# ProPrj_24_U202442553_2025-12-01.net
KiCad netlist of a schematic drawn in EasyEDA Pro
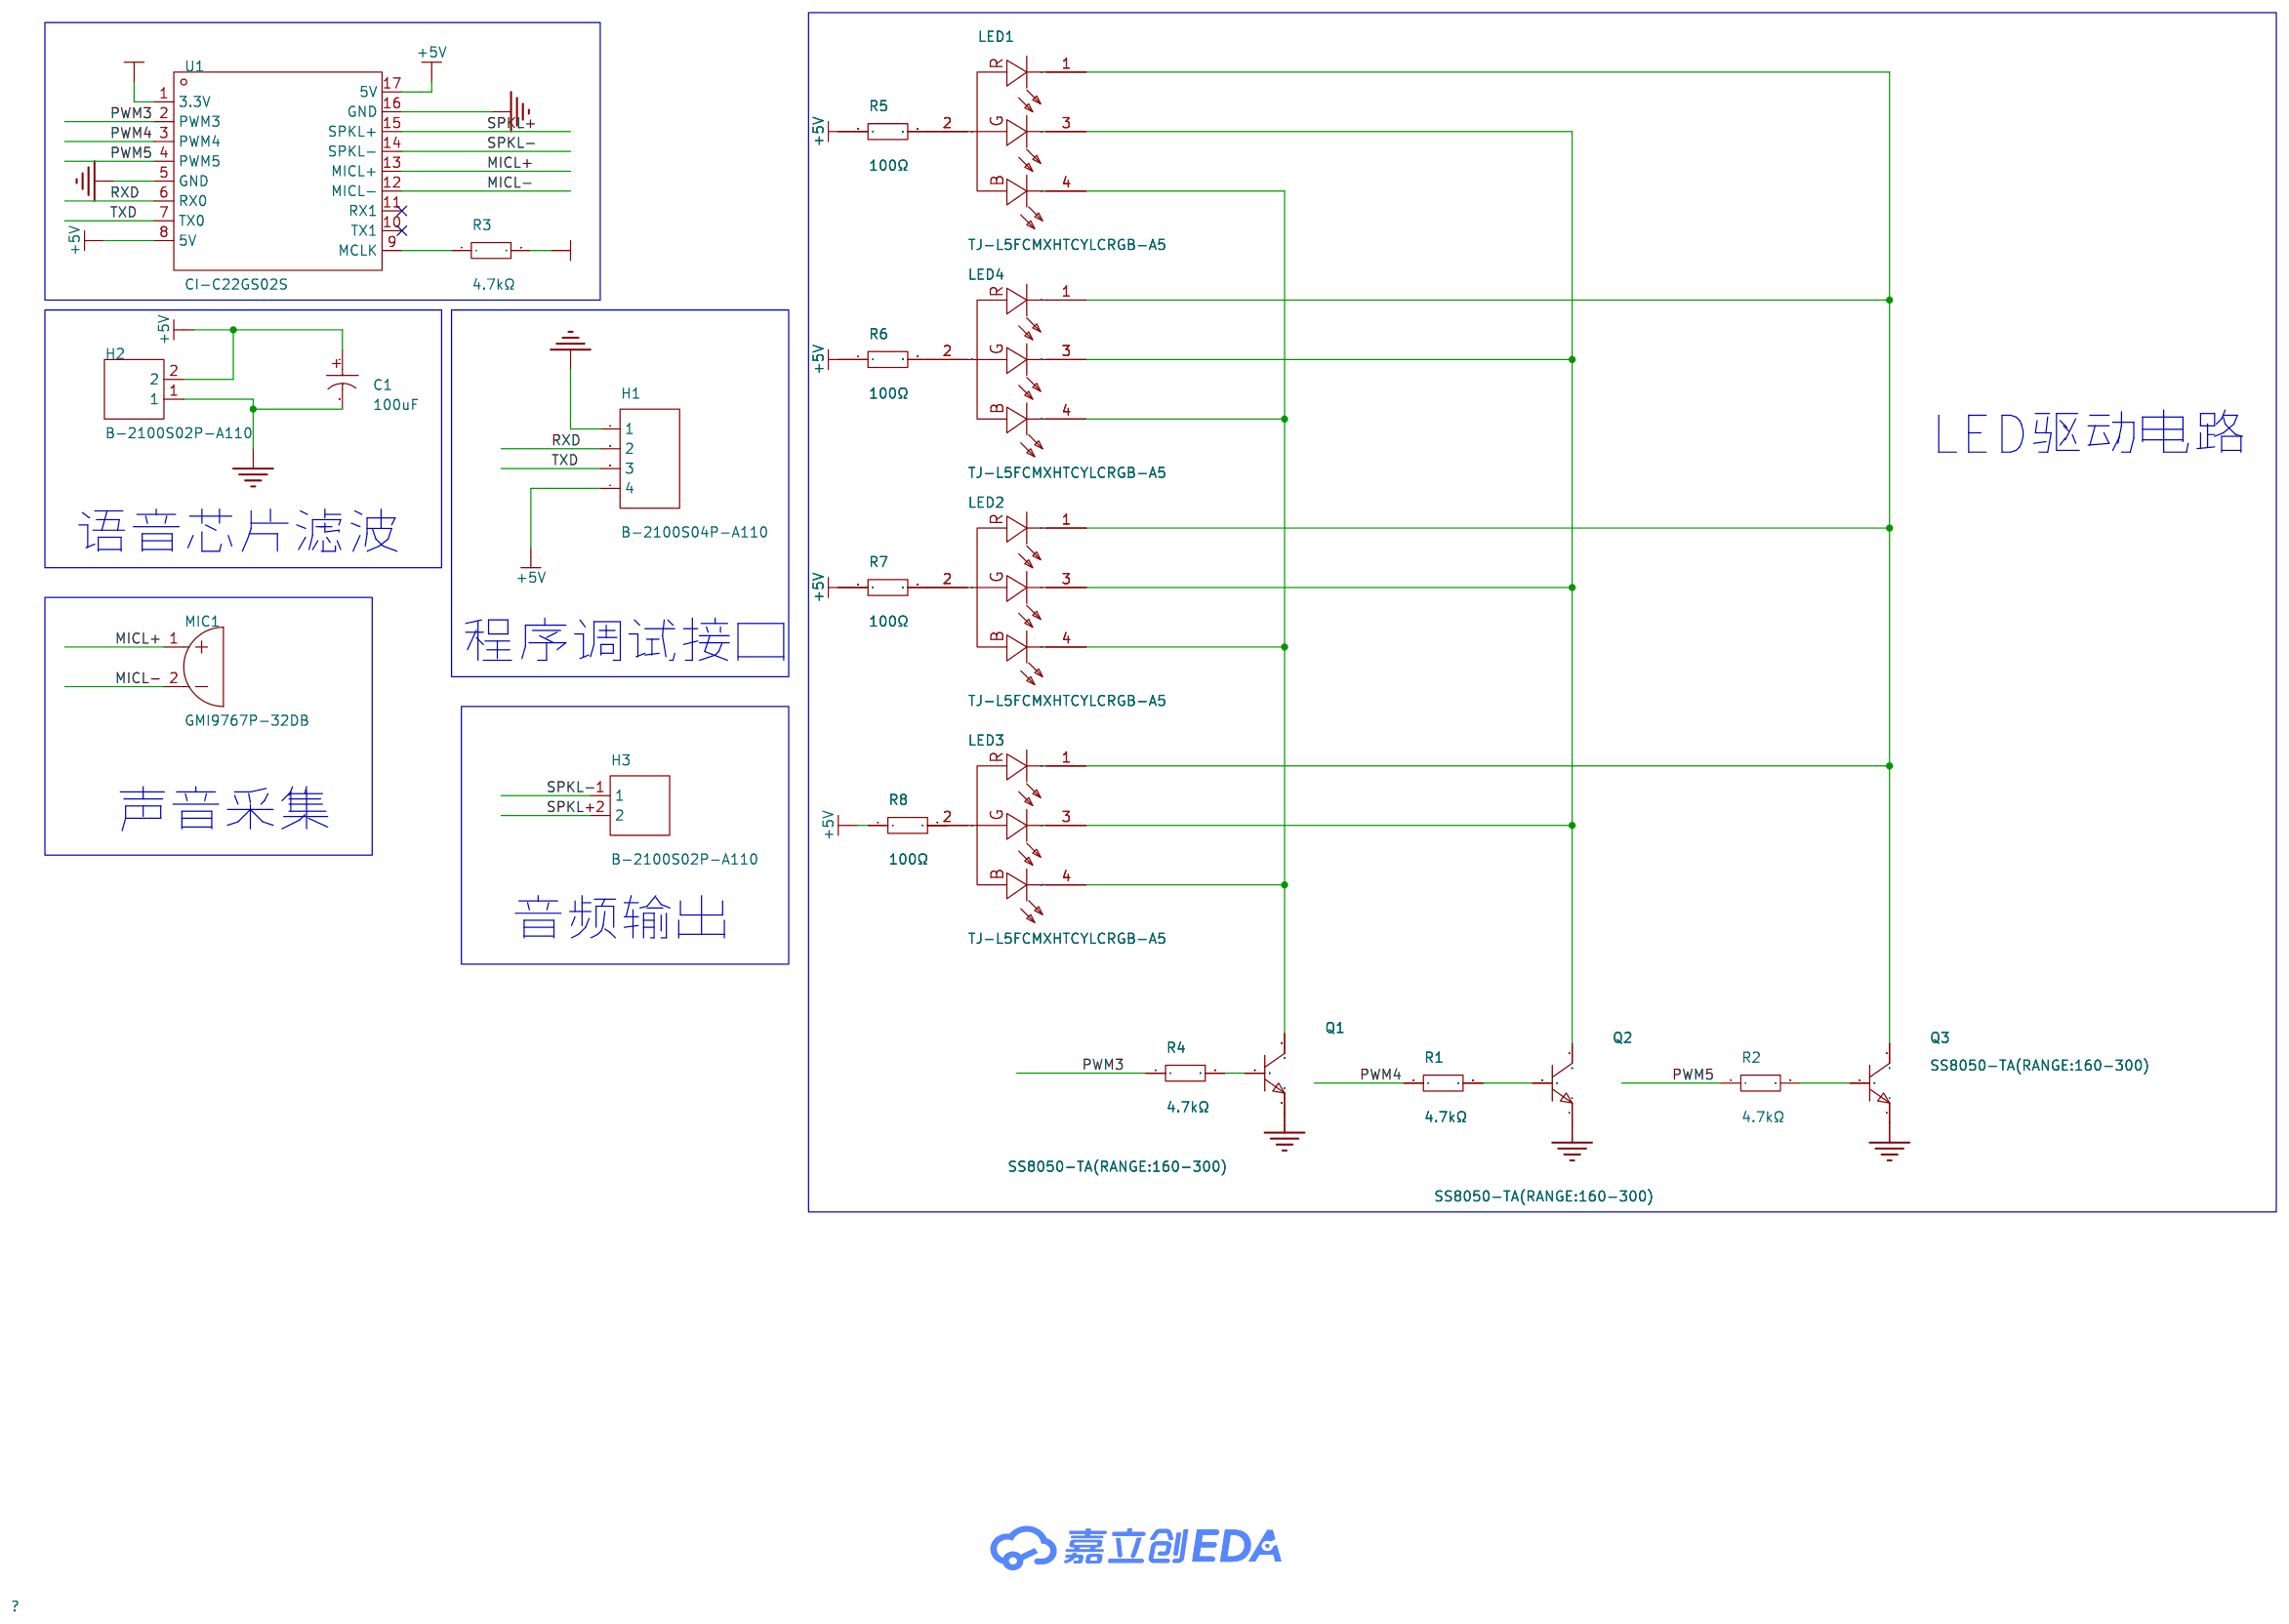
[diagram p0: schematic sheet]

(export (version "E")
  (design (tool "Eeschema 10.0.6"))
  (components
    (comp (ref "C1")
      (value "100uF")
      (footprint "easyedapro:CAP-TH_BD5.0-P2.00-D0.8-FD")
      (description "容值:100uF;精度:±20%;额定电压:16V;纹波电流:125mA@120Hz;等效串联电阻(ESR):-;")
      (fields
        (field (name "Manufacturer Part") "KM107M016D11RR0VH2FP0")
        (field (name "Manufacturer") "Chengx(承兴)")
      )
      (libsource (lib "easyedapro") (part "100uF 16V 5*11"))
    )
    (comp (ref "H1")
      (value "B-2100S04P-A110")
      (footprint "easyedapro:HDR-TH_4P-P2.54-V-M")
      (fields (field (name "Manufacturer") "Ckmtw(灿科盟)"))
      (libsource (lib "easyedapro") (part "Header-Male-2.54_1x4"))
    )
    (comp (ref "H2")
      (value "B-2100S02P-A110")
      (footprint "easyedapro:HDR-TH_2P-P2.54-V-M-1")
      (fields (field (name "Manufacturer") "Ckmtw(灿科盟)"))
      (libsource (lib "easyedapro") (part "210S-1*2P L=11.6MMGold-plated black"))
    )
    (comp (ref "H3")
      (value "B-2100S02P-A110")
      (footprint "easyedapro:HDR-TH_2P-P2.54-V-M-1")
      (fields (field (name "Manufacturer") "Ckmtw(灿科盟)"))
      (libsource (lib "easyedapro") (part "210S-1*2P L=11.6MMGold-plated black"))
    )
    (comp (ref "LED1")
      (value "TJ-L5FCMXHTCYLCRGB-A5")
      (footprint "easyedapro:LED-TH_4P-BD5.8-P1.30")
      (description "F5草帽RGB,直插RGB,F5草帽三色RGB")
      (fields (field (name "Manufacturer") "TOGIALED(统佳)"))
      (libsource (lib "easyedapro") (part "TJ-L5FCMXHTCYLCRGB-A5"))
    )
    (comp (ref "LED2")
      (value "TJ-L5FCMXHTCYLCRGB-A5")
      (footprint "easyedapro:LED-TH_4P-BD5.8-P1.30")
      (description "F5草帽RGB,直插RGB,F5草帽三色RGB")
      (fields (field (name "Manufacturer") "TOGIALED(统佳)"))
      (libsource (lib "easyedapro") (part "TJ-L5FCMXHTCYLCRGB-A5"))
    )
    (comp (ref "LED3")
      (value "TJ-L5FCMXHTCYLCRGB-A5")
      (footprint "easyedapro:LED-TH_4P-BD5.8-P1.30")
      (description "F5草帽RGB,直插RGB,F5草帽三色RGB")
      (fields (field (name "Manufacturer") "TOGIALED(统佳)"))
      (libsource (lib "easyedapro") (part "TJ-L5FCMXHTCYLCRGB-A5"))
    )
    (comp (ref "LED4")
      (value "TJ-L5FCMXHTCYLCRGB-A5")
      (footprint "easyedapro:LED-TH_4P-BD5.8-P1.30")
      (description "F5草帽RGB,直插RGB,F5草帽三色RGB")
      (fields (field (name "Manufacturer") "TOGIALED(统佳)"))
      (libsource (lib "easyedapro") (part "TJ-L5FCMXHTCYLCRGB-A5"))
    )
    (comp (ref "MIC1")
      (value "GMI9767P-32DB")
      (footprint "easyedapro:MIC-TH_BD9.7-P2.54-D0.8-L-FD")
      (description "指向性:全指向;输出阻抗:2.2kΩ;信噪比:58dB;灵敏度:-32dB;")
      (fields (field (name "Manufacturer") "INGHAi(赢海)"))
      (libsource (lib "easyedapro") (part "GMI9767P-32DB"))
    )
    (comp (ref "Q1")
      (value "SS8050-TA(RANGE:160-300)")
      (footprint "easyedapro:TO-92-3_L4.8-W3.7-P2.54-L")
      (description "晶体管类型:NPN;集电极电流(Ic):1.5A;集射极击穿电压(Vceo):25V;耗散功率(Pd):1W;直流电流增益(hFE):160@800mA,1V;")
      (fields (field (name "Manufacturer") "CJ(江苏长电/长晶)"))
      (libsource (lib "easyedapro") (part "SS8050_C80297"))
    )
    (comp (ref "Q2")
      (value "SS8050-TA(RANGE:160-300)")
      (footprint "easyedapro:TO-92-3_L4.8-W3.7-P2.54-L")
      (description "晶体管类型:NPN;集电极电流(Ic):1.5A;集射极击穿电压(Vceo):25V;耗散功率(Pd):1W;直流电流增益(hFE):160@800mA,1V;")
      (fields (field (name "Manufacturer") "CJ(江苏长电/长晶)"))
      (libsource (lib "easyedapro") (part "SS8050_C80297"))
    )
    (comp (ref "Q3")
      (value "SS8050-TA(RANGE:160-300)")
      (footprint "easyedapro:TO-92-3_L4.8-W3.7-P2.54-L")
      (description "晶体管类型:NPN;集电极电流(Ic):1.5A;集射极击穿电压(Vceo):25V;耗散功率(Pd):1W;直流电流增益(hFE):160@800mA,1V;")
      (fields (field (name "Manufacturer") "CJ(江苏长电/长晶)"))
      (libsource (lib "easyedapro") (part "SS8050_C80297"))
    )
    (comp (ref "R1")
      (value "4.7kΩ")
      (footprint "easyedapro:RES-TH_BD2.3-L6.5-P10.50-D0.5")
      (description "电阻类型:金属膜电阻;阻值:4.7kΩ;精度:±1%;功率:250mW;温度系数:±100ppm/°C;")
      (fields
        (field (name "Manufacturer Part") "MF1/4W-4.7KΩ±1% T")
        (field (name "Manufacturer") "CCO(千志电子)")
      )
      (libsource (lib "easyedapro") (part "MF1/4W-4.7KΩ±1% T52"))
    )
    (comp (ref "R2")
      (value "4.7kΩ")
      (footprint "easyedapro:RES-TH_BD2.3-L6.5-P10.50-D0.5")
      (description "电阻类型:金属膜电阻;阻值:4.7kΩ;精度:±1%;功率:250mW;温度系数:±100ppm/°C;")
      (fields
        (field (name "Manufacturer Part") "MF1/4W-4.7KΩ±1% T")
        (field (name "Manufacturer") "CCO(千志电子)")
      )
      (libsource (lib "easyedapro") (part "MF1/4W-4.7KΩ±1% T52"))
    )
    (comp (ref "R3")
      (value "4.7kΩ")
      (footprint "easyedapro:RES-TH_BD2.3-L6.5-P10.50-D0.5")
      (description "电阻类型:金属膜电阻;阻值:4.7kΩ;精度:±1%;功率:250mW;温度系数:±100ppm/°C;")
      (fields
        (field (name "Manufacturer Part") "MF1/4W-4.7KΩ±1% T")
        (field (name "Manufacturer") "CCO(千志电子)")
      )
      (libsource (lib "easyedapro") (part "MF1/4W-4.7KΩ±1% T52"))
    )
    (comp (ref "R4")
      (value "4.7kΩ")
      (footprint "easyedapro:RES-TH_BD2.3-L6.5-P10.50-D0.5")
      (description "电阻类型:金属膜电阻;阻值:4.7kΩ;精度:±1%;功率:250mW;温度系数:±100ppm/°C;")
      (fields
        (field (name "Manufacturer Part") "MF1/4W-4.7KΩ±1% T")
        (field (name "Manufacturer") "CCO(千志电子)")
      )
      (libsource (lib "easyedapro") (part "MF1/4W-4.7KΩ±1% T52"))
    )
    (comp (ref "R5")
      (value "100Ω")
      (footprint "easyedapro:RES-TH_BD3.3-L9.0-P13.00-D0.6")
      (description "电阻类型:金属膜电阻;阻值:100Ω;精度:±1%;功率:500mW;温度系数:±50ppm/°C;")
      (fields
        (field (name "Manufacturer Part") "RN1/2W100ΩFT/BA1")
        (field (name "Manufacturer") "Tyohm(幸亚电阻)")
      )
      (libsource (lib "easyedapro") (part "RN1/2W100ΩFT/BA1"))
    )
    (comp (ref "R6")
      (value "100Ω")
      (footprint "easyedapro:RES-TH_BD3.3-L9.0-P13.00-D0.6")
      (description "电阻类型:金属膜电阻;阻值:100Ω;精度:±1%;功率:500mW;温度系数:±50ppm/°C;")
      (fields
        (field (name "Manufacturer Part") "RN1/2W100ΩFT/BA1")
        (field (name "Manufacturer") "Tyohm(幸亚电阻)")
      )
      (libsource (lib "easyedapro") (part "RN1/2W100ΩFT/BA1"))
    )
    (comp (ref "R7")
      (value "100Ω")
      (footprint "easyedapro:RES-TH_BD3.3-L9.0-P13.00-D0.6")
      (description "电阻类型:金属膜电阻;阻值:100Ω;精度:±1%;功率:500mW;温度系数:±50ppm/°C;")
      (fields
        (field (name "Manufacturer Part") "RN1/2W100ΩFT/BA1")
        (field (name "Manufacturer") "Tyohm(幸亚电阻)")
      )
      (libsource (lib "easyedapro") (part "RN1/2W100ΩFT/BA1"))
    )
    (comp (ref "R8")
      (value "100Ω")
      (footprint "easyedapro:RES-TH_BD3.3-L9.0-P13.00-D0.6")
      (description "电阻类型:金属膜电阻;阻值:100Ω;精度:±1%;功率:500mW;温度系数:±50ppm/°C;")
      (fields
        (field (name "Manufacturer Part") "RN1/2W100ΩFT/BA1")
        (field (name "Manufacturer") "Tyohm(幸亚电阻)")
      )
      (libsource (lib "easyedapro") (part "RN1/2W100ΩFT/BA1"))
    )
    (comp (ref "U1")
      (value "CI-C22GS02S")
      (footprint "easyedapro:SMD-17_L20.0-W1.80-CI-C22GS02S")
      (description "长宽：18x20mm；带1路麦克风、1路喇叭和2路UART的接口、3路PWM接口。对外接口采用2排邮票孔和插针孔，方便采用回流贴片使用和焊接插针使用；支持离线语音识别（命令词条数：100条）")
      (fields (field (name "Manufacturer") "Chiplntelli(启英泰伦)"))
      (libsource (lib "easyedapro") (part "CI-C22GS02S"))
    )
  )
  (nets
    (net (code "1") (name "+5V") (class "Default")
      (node (ref "C1") (pin "1") (pinfunction "1_1") (pintype "input"))
      (node (ref "H1") (pin "4") (pinfunction "4_4") (pintype "unspecified"))
      (node (ref "H2") (pin "2") (pinfunction "2_2") (pintype "unspecified"))
      (node (ref "R5") (pin "1") (pinfunction "1_1") (pintype "unspecified"))
      (node (ref "R6") (pin "1") (pinfunction "1_1") (pintype "unspecified"))
      (node (ref "R7") (pin "1") (pinfunction "1_1") (pintype "unspecified"))
      (node (ref "R8") (pin "1") (pinfunction "1_1") (pintype "unspecified"))
      (node (ref "U1") (pin "17") (pinfunction "5V_17") (pintype "unspecified"))
      (node (ref "U1") (pin "8") (pinfunction "5V_8") (pintype "unspecified"))
    )
    (net (code "2") (name "/MICL+") (class "Default")
      (node (ref "MIC1") (pin "1") (pinfunction "1_1") (pintype "unspecified"))
      (node (ref "U1") (pin "13") (pinfunction "MICL+_13") (pintype "unspecified"))
    )
    (net (code "3") (name "/MICL-") (class "Default")
      (node (ref "MIC1") (pin "2") (pinfunction "2_2") (pintype "unspecified"))
      (node (ref "U1") (pin "12") (pinfunction "MICL-_12") (pintype "unspecified"))
    )
    (net (code "4") (name "/PWM3") (class "Default")
      (node (ref "R4") (pin "1") (pinfunction "1_1") (pintype "unspecified"))
      (node (ref "U1") (pin "2") (pinfunction "PWM3_2") (pintype "unspecified"))
    )
    (net (code "5") (name "/PWM4") (class "Default")
      (node (ref "R1") (pin "1") (pinfunction "1_1") (pintype "unspecified"))
      (node (ref "U1") (pin "3") (pinfunction "PWM4_3") (pintype "unspecified"))
    )
    (net (code "6") (name "/PWM5") (class "Default")
      (node (ref "R2") (pin "1") (pinfunction "1_1") (pintype "unspecified"))
      (node (ref "U1") (pin "4") (pinfunction "PWM5_4") (pintype "unspecified"))
    )
    (net (code "7") (name "/RXD") (class "Default")
      (node (ref "H1") (pin "2") (pinfunction "2_2") (pintype "unspecified"))
      (node (ref "U1") (pin "6") (pinfunction "RX0_6") (pintype "unspecified"))
    )
    (net (code "8") (name "/SPKL+") (class "Default")
      (node (ref "H3") (pin "2") (pinfunction "2_2") (pintype "unspecified"))
      (node (ref "U1") (pin "15") (pinfunction "SPKL+_15") (pintype "unspecified"))
    )
    (net (code "9") (name "/SPKL-") (class "Default")
      (node (ref "H3") (pin "1") (pinfunction "1_1") (pintype "unspecified"))
      (node (ref "U1") (pin "14") (pinfunction "SPKL-_14") (pintype "unspecified"))
    )
    (net (code "10") (name "/TXD") (class "Default")
      (node (ref "H1") (pin "3") (pinfunction "3_3") (pintype "unspecified"))
      (node (ref "U1") (pin "7") (pinfunction "TX0_7") (pintype "unspecified"))
    )
    (net (code "11") (name "3.3V") (class "Default")
      (node (ref "R3") (pin "2") (pinfunction "2_2") (pintype "unspecified"))
      (node (ref "U1") (pin "1") (pinfunction "3.3V_1") (pintype "unspecified"))
    )
    (net (code "12") (name "GND") (class "Default")
      (node (ref "C1") (pin "2") (pinfunction "2_2") (pintype "input"))
      (node (ref "H1") (pin "1") (pinfunction "1_1") (pintype "unspecified"))
      (node (ref "H2") (pin "1") (pinfunction "1_1") (pintype "unspecified"))
      (node (ref "Q1") (pin "1") (pinfunction "E_1") (pintype "unspecified"))
      (node (ref "Q2") (pin "1") (pinfunction "E_1") (pintype "unspecified"))
      (node (ref "Q3") (pin "1") (pinfunction "E_1") (pintype "unspecified"))
      (node (ref "U1") (pin "16") (pinfunction "GND_16") (pintype "unspecified"))
      (node (ref "U1") (pin "5") (pinfunction "GND_5") (pintype "unspecified"))
    )
    (net (code "13") (name "Net-(LED1-CA)") (class "Default")
      (node (ref "LED1") (pin "2") (pinfunction "CA_2") (pintype "unspecified"))
      (node (ref "R5") (pin "2") (pinfunction "2_2") (pintype "unspecified"))
    )
    (net (code "14") (name "Net-(LED1-KB)") (class "Default")
      (node (ref "LED1") (pin "4") (pinfunction "KB_4") (pintype "unspecified"))
      (node (ref "LED2") (pin "4") (pinfunction "KB_4") (pintype "unspecified"))
      (node (ref "LED3") (pin "4") (pinfunction "KB_4") (pintype "unspecified"))
      (node (ref "LED4") (pin "4") (pinfunction "KB_4") (pintype "unspecified"))
      (node (ref "Q1") (pin "3") (pinfunction "C_3") (pintype "unspecified"))
    )
    (net (code "15") (name "Net-(LED1-KG)") (class "Default")
      (node (ref "LED1") (pin "3") (pinfunction "KG_3") (pintype "unspecified"))
      (node (ref "LED2") (pin "3") (pinfunction "KG_3") (pintype "unspecified"))
      (node (ref "LED3") (pin "3") (pinfunction "KG_3") (pintype "unspecified"))
      (node (ref "LED4") (pin "3") (pinfunction "KG_3") (pintype "unspecified"))
      (node (ref "Q2") (pin "3") (pinfunction "C_3") (pintype "unspecified"))
    )
    (net (code "16") (name "Net-(LED1-KR)") (class "Default")
      (node (ref "LED1") (pin "1") (pinfunction "KR_1") (pintype "unspecified"))
      (node (ref "LED2") (pin "1") (pinfunction "KR_1") (pintype "unspecified"))
      (node (ref "LED3") (pin "1") (pinfunction "KR_1") (pintype "unspecified"))
      (node (ref "LED4") (pin "1") (pinfunction "KR_1") (pintype "unspecified"))
      (node (ref "Q3") (pin "3") (pinfunction "C_3") (pintype "unspecified"))
    )
    (net (code "17") (name "Net-(LED2-CA)") (class "Default")
      (node (ref "LED2") (pin "2") (pinfunction "CA_2") (pintype "unspecified"))
      (node (ref "R7") (pin "2") (pinfunction "2_2") (pintype "unspecified"))
    )
    (net (code "18") (name "Net-(LED3-CA)") (class "Default")
      (node (ref "LED3") (pin "2") (pinfunction "CA_2") (pintype "unspecified"))
      (node (ref "R8") (pin "2") (pinfunction "2_2") (pintype "unspecified"))
    )
    (net (code "19") (name "Net-(LED4-CA)") (class "Default")
      (node (ref "LED4") (pin "2") (pinfunction "CA_2") (pintype "unspecified"))
      (node (ref "R6") (pin "2") (pinfunction "2_2") (pintype "unspecified"))
    )
    (net (code "20") (name "Net-(Q1-B)") (class "Default")
      (node (ref "Q1") (pin "2") (pinfunction "B_2") (pintype "unspecified"))
      (node (ref "R4") (pin "2") (pinfunction "2_2") (pintype "unspecified"))
    )
    (net (code "21") (name "Net-(Q2-B)") (class "Default")
      (node (ref "Q2") (pin "2") (pinfunction "B_2") (pintype "unspecified"))
      (node (ref "R1") (pin "2") (pinfunction "2_2") (pintype "unspecified"))
    )
    (net (code "22") (name "Net-(Q3-B)") (class "Default")
      (node (ref "Q3") (pin "2") (pinfunction "B_2") (pintype "unspecified"))
      (node (ref "R2") (pin "2") (pinfunction "2_2") (pintype "unspecified"))
    )
    (net (code "23") (name "Net-(U1-MCLK)") (class "Default")
      (node (ref "R3") (pin "1") (pinfunction "1_1") (pintype "unspecified"))
      (node (ref "U1") (pin "9") (pinfunction "MCLK_9") (pintype "unspecified"))
    )
    (net (code "24") (name "unconnected-(U1-RX1-Pad11)") (class "Default")
      (node (ref "U1") (pin "11") (pinfunction "RX1_11") (pintype "unspecified+no_connect"))
    )
    (net (code "25") (name "unconnected-(U1-TX1-Pad10)") (class "Default")
      (node (ref "U1") (pin "10") (pinfunction "TX1_10") (pintype "unspecified+no_connect"))
    )
  )
)
